# ADC_AD7761BSTZ.net
KiCad netlist of a schematic drawn in EAGLE
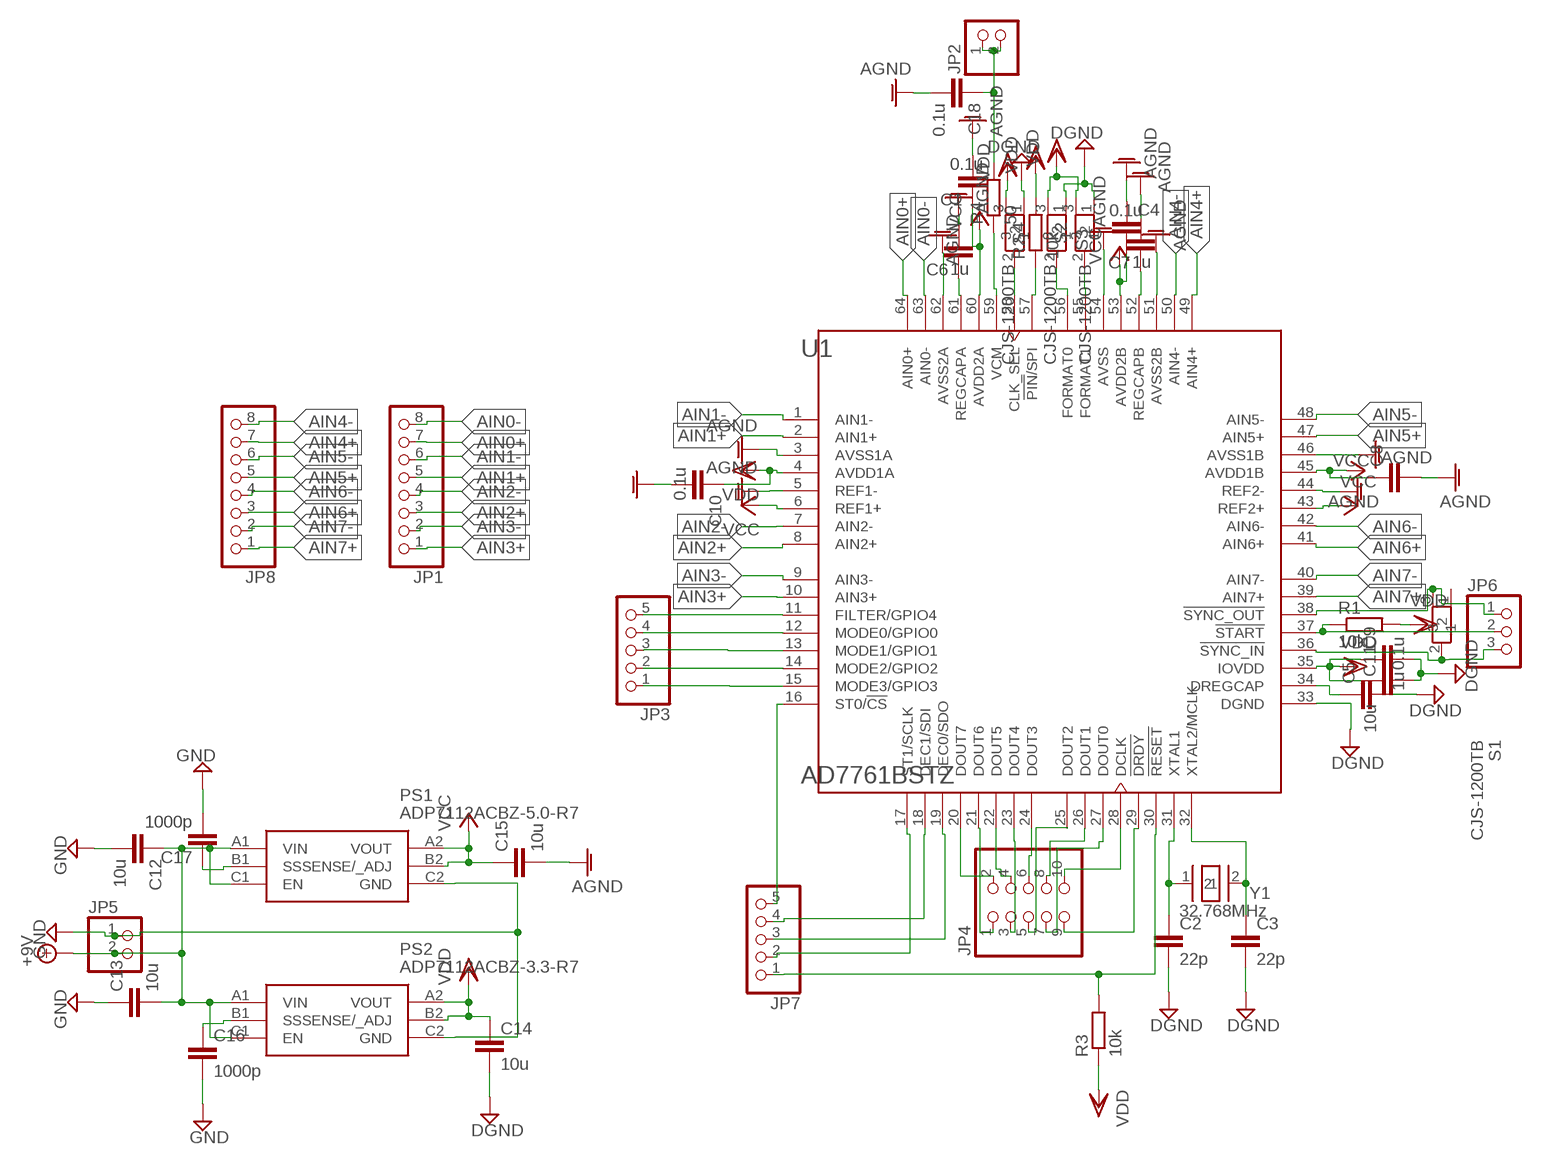
[diagram p0: schematic, sheet 1]

(export (version "E")
  (design (tool "Eeschema 10.0.6"))
  (components
    (comp (ref "C1")
      (value "0.1u")
      (footprint "eagle-import:C1608")
      (libsource (lib "eagle-import") (part "C-EUC1608"))
    )
    (comp (ref "C2")
      (value "22p")
      (footprint "eagle-import:C1608")
      (libsource (lib "eagle-import") (part "C-EUC1608"))
    )
    (comp (ref "C3")
      (value "22p")
      (footprint "eagle-import:C1608")
      (libsource (lib "eagle-import") (part "C-EUC1608"))
    )
    (comp (ref "C4")
      (value "0.1u")
      (footprint "eagle-import:C1608")
      (libsource (lib "eagle-import") (part "C-EUC1608"))
    )
    (comp (ref "C5")
      (value "10u")
      (footprint "eagle-import:C2012")
      (libsource (lib "eagle-import") (part "C-EUC2012"))
    )
    (comp (ref "C6")
      (value "1u")
      (footprint "eagle-import:C1608")
      (libsource (lib "eagle-import") (part "C-EUC1608"))
    )
    (comp (ref "C7")
      (value "1u")
      (footprint "eagle-import:C1608")
      (libsource (lib "eagle-import") (part "C-EUC1608"))
    )
    (comp (ref "C8")
      (value "0.1u")
      (footprint "eagle-import:C1608")
      (libsource (lib "eagle-import") (part "C-EUC1608"))
    )
    (comp (ref "C9")
      (value "0.1u")
      (footprint "eagle-import:C1608")
      (libsource (lib "eagle-import") (part "C-EUC1608"))
    )
    (comp (ref "C10")
      (value "0.1u")
      (footprint "eagle-import:C1608")
      (libsource (lib "eagle-import") (part "C-EUC1608"))
    )
    (comp (ref "C11")
      (value "1u")
      (footprint "eagle-import:C1608")
      (libsource (lib "eagle-import") (part "C-EUC1608"))
    )
    (comp (ref "C12")
      (value "10u")
      (footprint "eagle-import:C2012")
      (libsource (lib "eagle-import") (part "C-EUC2012"))
    )
    (comp (ref "C13")
      (value "10u")
      (footprint "eagle-import:C2012")
      (libsource (lib "eagle-import") (part "C-EUC2012"))
    )
    (comp (ref "C14")
      (value "10u")
      (footprint "eagle-import:C2012")
      (libsource (lib "eagle-import") (part "C-EUC2012"))
    )
    (comp (ref "C15")
      (value "10u")
      (footprint "eagle-import:C2012")
      (libsource (lib "eagle-import") (part "C-EUC2012"))
    )
    (comp (ref "C16")
      (value "1000p")
      (footprint "eagle-import:C1608")
      (libsource (lib "eagle-import") (part "C-EUC1608"))
    )
    (comp (ref "C17")
      (value "1000p")
      (footprint "eagle-import:C1608")
      (libsource (lib "eagle-import") (part "C-EUC1608"))
    )
    (comp (ref "C18")
      (value "0.1u")
      (footprint "eagle-import:C1608")
      (libsource (lib "eagle-import") (part "C-EUC1608"))
    )
    (comp (ref "JP1")
      (value "PINHD-1X8")
      (footprint "eagle-import:1X08")
      (libsource (lib "eagle-import") (part "PINHD-1X8"))
    )
    (comp (ref "JP2")
      (value "PINHD-1X2")
      (footprint "eagle-import:1X02")
      (libsource (lib "eagle-import") (part "PINHD-1X2"))
    )
    (comp (ref "JP3")
      (value "PINHD-1X5")
      (footprint "eagle-import:1X05")
      (libsource (lib "eagle-import") (part "PINHD-1X5"))
    )
    (comp (ref "JP4")
      (value "PINHD-2X5")
      (footprint "eagle-import:2X05")
      (libsource (lib "eagle-import") (part "PINHD-2X5"))
    )
    (comp (ref "JP5")
      (value "PINHD-1X2")
      (footprint "eagle-import:1X02")
      (libsource (lib "eagle-import") (part "PINHD-1X2"))
    )
    (comp (ref "JP6")
      (value "PINHD-1X3")
      (footprint "eagle-import:1X03")
      (libsource (lib "eagle-import") (part "PINHD-1X3"))
    )
    (comp (ref "JP7")
      (value "PINHD-1X5")
      (footprint "eagle-import:1X05")
      (libsource (lib "eagle-import") (part "PINHD-1X5"))
    )
    (comp (ref "JP8")
      (value "PINHD-1X8")
      (footprint "eagle-import:1X08")
      (libsource (lib "eagle-import") (part "PINHD-1X8"))
    )
    (comp (ref "PS1")
      (value "ADP7112ACBZ-5.0-R7")
      (footprint "eagle-import:BGA6C40P2X3_95X116X56")
      (fields
        (field (name "ARROW_PART_NUMBER") "ADP7112ACBZ-3.3-R7")
        (field (name "MOUSER_PART_NUMBER") "584-ADP7112ACBZ3.3R7")
      )
      (libsource (lib "eagle-import") (part "ADP7112ACBZ-3.3-R7"))
    )
    (comp (ref "PS2")
      (value "ADP7112ACBZ-3.3-R7")
      (footprint "eagle-import:BGA6C40P2X3_95X116X56")
      (fields (field (name "MOUSER_PART_NUMBER") "584-ADP7112ACBZ3.3R7"))
      (libsource (lib "eagle-import") (part "ADP7112ACBZ-3.3-R7"))
    )
    (comp (ref "R1")
      (value "10k")
      (footprint "eagle-import:R0603")
      (libsource (lib "eagle-import") (part "R-EU_R0603"))
    )
    (comp (ref "R2")
      (value "10k")
      (footprint "eagle-import:R0603")
      (libsource (lib "eagle-import") (part "R-EU_R0603"))
    )
    (comp (ref "R3")
      (value "10k")
      (footprint "eagle-import:R0603")
      (libsource (lib "eagle-import") (part "R-EU_R0603"))
    )
    (comp (ref "R4")
      (value "50")
      (footprint "eagle-import:R0603")
      (libsource (lib "eagle-import") (part "R-EU_R0603"))
    )
    (comp (ref "S1")
      (value "CJS-1200TB")
      (footprint "eagle-import:B-TYPE")
      (libsource (lib "eagle-import") (part "CJS-1200TB"))
    )
    (comp (ref "S2")
      (value "CJS-1200TB")
      (footprint "eagle-import:B-TYPE")
      (libsource (lib "eagle-import") (part "CJS-1200TB"))
    )
    (comp (ref "S3")
      (value "CJS-1200TB")
      (footprint "eagle-import:B-TYPE")
      (libsource (lib "eagle-import") (part "CJS-1200TB"))
    )
    (comp (ref "S4")
      (value "CJS-1200TB")
      (footprint "eagle-import:B-TYPE")
      (libsource (lib "eagle-import") (part "CJS-1200TB"))
    )
    (comp (ref "U1")
      (value "AD7761BSTZ")
      (footprint "eagle-import:QFP50P1200X1200X160-64N")
      (fields (field (name "MF") "Analog Devices"))
      (libsource (lib "eagle-import") (part "AD7761BSTZ"))
    )
    (comp (ref "Y1")
      (value "32.768MHz")
      (footprint "eagle-import:FC4SDCBMF24576T1")
      (fields
        (field (name "ARROW_PART_NUMBER") "FC4SDCBMF24.576-T1")
        (field (name "MOUSER_PART_NUMBER") "559-FC4SDCBMF24576T1")
      )
      (libsource (lib "eagle-import") (part "FC4SDCBMF24.576-T1"))
    )
  )
  (nets
    (net (code "1") (name "+9V") (class "Default")
      (node (ref "C12") (pin "1") (pinfunction "1_1") (pintype "passive"))
      (node (ref "C13") (pin "2") (pinfunction "2_2") (pintype "passive"))
      (node (ref "JP5") (pin "2") (pinfunction "2_2") (pintype "passive"))
      (node (ref "PS1") (pin "A1") (pinfunction "VIN_A1") (pintype "bidirectional"))
      (node (ref "PS1") (pin "C1") (pinfunction "EN_C1") (pintype "bidirectional"))
      (node (ref "PS2") (pin "A1") (pinfunction "VIN_A1") (pintype "bidirectional"))
      (node (ref "PS2") (pin "C1") (pinfunction "EN_C1") (pintype "bidirectional"))
    )
    (net (code "2") (name "AGND") (class "Default")
      (node (ref "C1") (pin "2") (pinfunction "2_2") (pintype "passive"))
      (node (ref "C10") (pin "2") (pinfunction "2_2") (pintype "passive"))
      (node (ref "C15") (pin "2") (pinfunction "2_2") (pintype "passive"))
      (node (ref "C18") (pin "2") (pinfunction "2_2") (pintype "passive"))
      (node (ref "C4") (pin "1") (pinfunction "1_1") (pintype "passive"))
      (node (ref "C6") (pin "2") (pinfunction "2_2") (pintype "passive"))
      (node (ref "C7") (pin "2") (pinfunction "2_2") (pintype "passive"))
      (node (ref "C8") (pin "2") (pinfunction "2_2") (pintype "passive"))
      (node (ref "U1") (pin "3") (pinfunction "AVSS1A_3") (pintype "power_in"))
      (node (ref "U1") (pin "44") (pinfunction "REF2-_44") (pintype "input"))
      (node (ref "U1") (pin "46") (pinfunction "AVSS1B_46") (pintype "power_in"))
      (node (ref "U1") (pin "5") (pinfunction "REF1-_5") (pintype "input"))
      (node (ref "U1") (pin "51") (pinfunction "AVSS2B_51") (pintype "power_in"))
      (node (ref "U1") (pin "54") (pinfunction "AVSS_54") (pintype "power_in"))
      (node (ref "U1") (pin "62") (pinfunction "AVSS2A_62") (pintype "power_in"))
    )
    (net (code "3") (name "AIN0+") (class "Default")
      (node (ref "JP1") (pin "7") (pinfunction "7_7") (pintype "passive"))
      (node (ref "U1") (pin "64") (pinfunction "AIN0+_64") (pintype "input"))
    )
    (net (code "4") (name "AIN0-") (class "Default")
      (node (ref "JP1") (pin "8") (pinfunction "8_8") (pintype "passive"))
      (node (ref "U1") (pin "63") (pinfunction "AIN0-_63") (pintype "input"))
    )
    (net (code "5") (name "AIN1+") (class "Default")
      (node (ref "JP1") (pin "5") (pinfunction "5_5") (pintype "passive"))
      (node (ref "U1") (pin "2") (pinfunction "AIN1+_2") (pintype "input"))
    )
    (net (code "6") (name "AIN1-") (class "Default")
      (node (ref "JP1") (pin "6") (pinfunction "6_6") (pintype "passive"))
      (node (ref "U1") (pin "1") (pinfunction "AIN1-_1") (pintype "input"))
    )
    (net (code "7") (name "AIN2+") (class "Default")
      (node (ref "JP1") (pin "3") (pinfunction "3_3") (pintype "passive"))
      (node (ref "U1") (pin "8") (pinfunction "AIN2+_8") (pintype "input"))
    )
    (net (code "8") (name "AIN2-") (class "Default")
      (node (ref "JP1") (pin "4") (pinfunction "4_4") (pintype "passive"))
      (node (ref "U1") (pin "7") (pinfunction "AIN2-_7") (pintype "input"))
    )
    (net (code "9") (name "AIN3+") (class "Default")
      (node (ref "JP1") (pin "1") (pinfunction "1_1") (pintype "passive"))
      (node (ref "U1") (pin "10") (pinfunction "AIN3+_10") (pintype "input"))
    )
    (net (code "10") (name "AIN3-") (class "Default")
      (node (ref "JP1") (pin "2") (pinfunction "2_2") (pintype "passive"))
      (node (ref "U1") (pin "9") (pinfunction "AIN3-_9") (pintype "input"))
    )
    (net (code "11") (name "AIN4+") (class "Default")
      (node (ref "JP8") (pin "7") (pinfunction "7_7") (pintype "passive"))
      (node (ref "U1") (pin "49") (pinfunction "AIN4+_49") (pintype "input"))
    )
    (net (code "12") (name "AIN4-") (class "Default")
      (node (ref "JP8") (pin "8") (pinfunction "8_8") (pintype "passive"))
      (node (ref "U1") (pin "50") (pinfunction "AIN4-_50") (pintype "input"))
    )
    (net (code "13") (name "AIN5+") (class "Default")
      (node (ref "JP8") (pin "5") (pinfunction "5_5") (pintype "passive"))
      (node (ref "U1") (pin "47") (pinfunction "AIN5+_47") (pintype "input"))
    )
    (net (code "14") (name "AIN5-") (class "Default")
      (node (ref "JP8") (pin "6") (pinfunction "6_6") (pintype "passive"))
      (node (ref "U1") (pin "48") (pinfunction "AIN5-_48") (pintype "input"))
    )
    (net (code "15") (name "AIN6+") (class "Default")
      (node (ref "JP8") (pin "3") (pinfunction "3_3") (pintype "passive"))
      (node (ref "U1") (pin "41") (pinfunction "AIN6+_41") (pintype "input"))
    )
    (net (code "16") (name "AIN6-") (class "Default")
      (node (ref "JP8") (pin "4") (pinfunction "4_4") (pintype "passive"))
      (node (ref "U1") (pin "42") (pinfunction "AIN6-_42") (pintype "input"))
    )
    (net (code "17") (name "AIN7+") (class "Default")
      (node (ref "JP8") (pin "1") (pinfunction "1_1") (pintype "passive"))
      (node (ref "U1") (pin "39") (pinfunction "AIN7+_39") (pintype "input"))
    )
    (net (code "18") (name "AIN7-") (class "Default")
      (node (ref "JP8") (pin "2") (pinfunction "2_2") (pintype "passive"))
      (node (ref "U1") (pin "40") (pinfunction "AIN7-_40") (pintype "input"))
    )
    (net (code "19") (name "DGND") (class "Default")
      (node (ref "C11") (pin "2") (pinfunction "2_2") (pintype "passive"))
      (node (ref "C14") (pin "2") (pinfunction "2_2") (pintype "passive"))
      (node (ref "C2") (pin "2") (pinfunction "2_2") (pintype "passive"))
      (node (ref "C3") (pin "2") (pinfunction "2_2") (pintype "passive"))
      (node (ref "C5") (pin "2") (pinfunction "2_2") (pintype "passive"))
      (node (ref "C9") (pin "2") (pinfunction "2_2") (pintype "passive"))
      (node (ref "S2") (pin "1") (pinfunction "1_1") (pintype "bidirectional"))
      (node (ref "S3") (pin "1") (pinfunction "1_1") (pintype "bidirectional"))
      (node (ref "S4") (pin "1") (pinfunction "1_1") (pintype "bidirectional"))
      (node (ref "U1") (pin "33") (pinfunction "DGND_33") (pintype "power_in"))
    )
    (net (code "20") (name "GND") (class "Default")
      (node (ref "C12") (pin "2") (pinfunction "2_2") (pintype "passive"))
      (node (ref "C13") (pin "1") (pinfunction "1_1") (pintype "passive"))
      (node (ref "C16") (pin "2") (pinfunction "2_2") (pintype "passive"))
      (node (ref "C17") (pin "2") (pinfunction "2_2") (pintype "passive"))
      (node (ref "JP5") (pin "1") (pinfunction "1_1") (pintype "passive"))
      (node (ref "PS1") (pin "C2") (pinfunction "GND_C2") (pintype "bidirectional"))
      (node (ref "PS2") (pin "C2") (pinfunction "GND_C2") (pintype "bidirectional"))
    )
    (net (code "21") (name "Net-(C18-Pad1)") (class "Default")
      (node (ref "C18") (pin "1") (pinfunction "1_1") (pintype "passive"))
      (node (ref "JP2") (pin "1") (pinfunction "1_1") (pintype "passive"))
      (node (ref "JP2") (pin "2") (pinfunction "2_2") (pintype "passive"))
      (node (ref "R4") (pin "2") (pinfunction "2_2") (pintype "passive"))
    )
    (net (code "22") (name "Net-(PS1-SS)") (class "Default")
      (node (ref "C17") (pin "1") (pinfunction "1_1") (pintype "passive"))
      (node (ref "PS1") (pin "B1") (pinfunction "SS_B1") (pintype "bidirectional"))
    )
    (net (code "23") (name "Net-(PS2-SS)") (class "Default")
      (node (ref "C16") (pin "1") (pinfunction "1_1") (pintype "passive"))
      (node (ref "PS2") (pin "B1") (pinfunction "SS_B1") (pintype "bidirectional"))
    )
    (net (code "24") (name "Net-(U1-CLK_SEL)") (class "Default")
      (node (ref "S4") (pin "2") (pinfunction "2_2") (pintype "bidirectional"))
      (node (ref "U1") (pin "58") (pinfunction "CLK_SEL_58") (pintype "input"))
    )
    (net (code "25") (name "Net-(U1-DCLK)") (class "Default")
      (node (ref "JP4") (pin "10") (pinfunction "10_10") (pintype "passive"))
      (node (ref "U1") (pin "28") (pinfunction "DCLK_28") (pintype "output"))
    )
    (net (code "26") (name "Net-(U1-DEC0{slash}SDO)") (class "Default")
      (node (ref "JP7") (pin "3") (pinfunction "3_3") (pintype "passive"))
      (node (ref "U1") (pin "19") (pinfunction "DEC0/SDO_19") (pintype "bidirectional"))
    )
    (net (code "27") (name "Net-(U1-DEC1{slash}SDI)") (class "Default")
      (node (ref "JP7") (pin "4") (pinfunction "4_4") (pintype "passive"))
      (node (ref "U1") (pin "18") (pinfunction "DEC1/SDI_18") (pintype "input"))
    )
    (net (code "28") (name "Net-(U1-DOUT0)") (class "Default")
      (node (ref "JP4") (pin "7") (pinfunction "7_7") (pintype "passive"))
      (node (ref "U1") (pin "27") (pinfunction "DOUT0_27") (pintype "output"))
    )
    (net (code "29") (name "Net-(U1-DOUT1)") (class "Default")
      (node (ref "JP4") (pin "8") (pinfunction "8_8") (pintype "passive"))
      (node (ref "U1") (pin "26") (pinfunction "DOUT1_26") (pintype "output"))
    )
    (net (code "30") (name "Net-(U1-DOUT2)") (class "Default")
      (node (ref "JP4") (pin "5") (pinfunction "5_5") (pintype "passive"))
      (node (ref "U1") (pin "25") (pinfunction "DOUT2_25") (pintype "output"))
    )
    (net (code "31") (name "Net-(U1-DOUT3)") (class "Default")
      (node (ref "JP4") (pin "6") (pinfunction "6_6") (pintype "passive"))
      (node (ref "U1") (pin "24") (pinfunction "DOUT3_24") (pintype "output"))
    )
    (net (code "32") (name "Net-(U1-DOUT4)") (class "Default")
      (node (ref "JP4") (pin "3") (pinfunction "3_3") (pintype "passive"))
      (node (ref "U1") (pin "23") (pinfunction "DOUT4_23") (pintype "output"))
    )
    (net (code "33") (name "Net-(U1-DOUT5)") (class "Default")
      (node (ref "JP4") (pin "4") (pinfunction "4_4") (pintype "passive"))
      (node (ref "U1") (pin "22") (pinfunction "DOUT5_22") (pintype "output"))
    )
    (net (code "34") (name "Net-(U1-DOUT6)") (class "Default")
      (node (ref "JP4") (pin "1") (pinfunction "1_1") (pintype "passive"))
      (node (ref "U1") (pin "21") (pinfunction "DOUT6_21") (pintype "output"))
    )
    (net (code "35") (name "Net-(U1-DOUT7)") (class "Default")
      (node (ref "JP4") (pin "2") (pinfunction "2_2") (pintype "passive"))
      (node (ref "U1") (pin "20") (pinfunction "DOUT7_20") (pintype "output"))
    )
    (net (code "36") (name "Net-(U1-DREGCAP)") (class "Default")
      (node (ref "C5") (pin "1") (pinfunction "1_1") (pintype "passive"))
      (node (ref "U1") (pin "34") (pinfunction "DREGCAP_34") (pintype "output"))
    )
    (net (code "37") (name "Net-(U1-FILTER{slash}GPIO4)") (class "Default")
      (node (ref "JP3") (pin "5") (pinfunction "5_5") (pintype "passive"))
      (node (ref "U1") (pin "11") (pinfunction "FILTER/GPIO4_11") (pintype "bidirectional"))
    )
    (net (code "38") (name "Net-(U1-FORMAT0)") (class "Default")
      (node (ref "S2") (pin "2") (pinfunction "2_2") (pintype "bidirectional"))
      (node (ref "U1") (pin "56") (pinfunction "FORMAT0_56") (pintype "input"))
    )
    (net (code "39") (name "Net-(U1-FORMAT1)") (class "Default")
      (node (ref "S3") (pin "2") (pinfunction "2_2") (pintype "bidirectional"))
      (node (ref "U1") (pin "55") (pinfunction "FORMAT1_55") (pintype "input"))
    )
    (net (code "40") (name "Net-(U1-MODE0{slash}GPIO0)") (class "Default")
      (node (ref "JP3") (pin "4") (pinfunction "4_4") (pintype "passive"))
      (node (ref "U1") (pin "12") (pinfunction "MODE0/GPIO0_12") (pintype "bidirectional"))
    )
    (net (code "41") (name "Net-(U1-MODE1{slash}GPIO1)") (class "Default")
      (node (ref "JP3") (pin "3") (pinfunction "3_3") (pintype "passive"))
      (node (ref "U1") (pin "13") (pinfunction "MODE1/GPIO1_13") (pintype "bidirectional"))
    )
    (net (code "42") (name "Net-(U1-MODE2{slash}GPIO2)") (class "Default")
      (node (ref "JP3") (pin "2") (pinfunction "2_2") (pintype "passive"))
      (node (ref "U1") (pin "14") (pinfunction "MODE2/GPIO2_14") (pintype "bidirectional"))
    )
    (net (code "43") (name "Net-(U1-MODE3{slash}GPIO3)") (class "Default")
      (node (ref "JP3") (pin "1") (pinfunction "1_1") (pintype "passive"))
      (node (ref "U1") (pin "15") (pinfunction "MODE3/GPIO3_15") (pintype "bidirectional"))
    )
    (net (code "44") (name "Net-(U1-REGCAPA)") (class "Default")
      (node (ref "C6") (pin "1") (pinfunction "1_1") (pintype "passive"))
      (node (ref "U1") (pin "61") (pinfunction "REGCAPA_61") (pintype "output"))
    )
    (net (code "45") (name "Net-(U1-REGCAPB)") (class "Default")
      (node (ref "C7") (pin "1") (pinfunction "1_1") (pintype "passive"))
      (node (ref "U1") (pin "52") (pinfunction "REGCAPB_52") (pintype "output"))
    )
    (net (code "46") (name "Net-(U1-ST0{slash}~{CS})") (class "Default")
      (node (ref "JP7") (pin "5") (pinfunction "5_5") (pintype "passive"))
      (node (ref "U1") (pin "16") (pinfunction "ST0/~{CS}_16") (pintype "input"))
    )
    (net (code "47") (name "Net-(U1-ST1{slash}SCLK)") (class "Default")
      (node (ref "JP7") (pin "2") (pinfunction "2_2") (pintype "passive"))
      (node (ref "U1") (pin "17") (pinfunction "ST1/SCLK_17") (pintype "input"))
    )
    (net (code "48") (name "Net-(U1-VCM)") (class "Default")
      (node (ref "R4") (pin "1") (pinfunction "1_1") (pintype "passive"))
      (node (ref "U1") (pin "59") (pinfunction "VCM_59") (pintype "output"))
    )
    (net (code "49") (name "Net-(U1-XTAL1)") (class "Default")
      (node (ref "C2") (pin "1") (pinfunction "1_1") (pintype "passive"))
      (node (ref "U1") (pin "31") (pinfunction "XTAL1_31") (pintype "input"))
      (node (ref "Y1") (pin "1") (pinfunction "1_1") (pintype "bidirectional"))
    )
    (net (code "50") (name "Net-(U1-XTAL2{slash}MCLK)") (class "Default")
      (node (ref "C3") (pin "1") (pinfunction "1_1") (pintype "passive"))
      (node (ref "U1") (pin "32") (pinfunction "XTAL2/MCLK_32") (pintype "input"))
      (node (ref "Y1") (pin "2") (pinfunction "2_2") (pintype "bidirectional"))
    )
    (net (code "51") (name "Net-(U1-~{DRDY})") (class "Default")
      (node (ref "JP4") (pin "9") (pinfunction "9_9") (pintype "passive"))
      (node (ref "U1") (pin "29") (pinfunction "~{DRDY}_29") (pintype "output"))
    )
    (net (code "52") (name "Net-(U1-~{PIN}{slash}SPI)") (class "Default")
      (node (ref "R2") (pin "1") (pinfunction "1_1") (pintype "passive"))
      (node (ref "U1") (pin "57") (pinfunction "~{PIN}/SPI_57") (pintype "input"))
    )
    (net (code "53") (name "Net-(U1-~{RESET})") (class "Default")
      (node (ref "JP7") (pin "1") (pinfunction "1_1") (pintype "passive"))
      (node (ref "R3") (pin "2") (pinfunction "2_2") (pintype "passive"))
      (node (ref "U1") (pin "30") (pinfunction "~{RESET}_30") (pintype "input"))
    )
    (net (code "54") (name "Net-(U1-~{START})") (class "Default")
      (node (ref "JP6") (pin "2") (pinfunction "2_2") (pintype "passive"))
      (node (ref "R1") (pin "1") (pinfunction "1_1") (pintype "passive"))
      (node (ref "U1") (pin "37") (pinfunction "~{START}_37") (pintype "input"))
    )
    (net (code "55") (name "Net-(U1-~{SYNC_IN})") (class "Default")
      (node (ref "JP6") (pin "3") (pinfunction "3_3") (pintype "passive"))
      (node (ref "S1") (pin "2") (pinfunction "2_2") (pintype "bidirectional"))
      (node (ref "U1") (pin "36") (pinfunction "~{SYNC_IN}_36") (pintype "input"))
    )
    (net (code "56") (name "Net-(U1-~{SYNC_OUT})") (class "Default")
      (node (ref "JP6") (pin "1") (pinfunction "1_1") (pintype "passive"))
      (node (ref "S1") (pin "3") (pinfunction "3_3") (pintype "bidirectional"))
      (node (ref "U1") (pin "38") (pinfunction "~{SYNC_OUT}_38") (pintype "output"))
    )
    (net (code "57") (name "VCC") (class "Default")
      (node (ref "C1") (pin "1") (pinfunction "1_1") (pintype "passive"))
      (node (ref "C15") (pin "1") (pinfunction "1_1") (pintype "passive"))
      (node (ref "C4") (pin "2") (pinfunction "2_2") (pintype "passive"))
      (node (ref "C8") (pin "1") (pinfunction "1_1") (pintype "passive"))
      (node (ref "PS1") (pin "A2") (pinfunction "VOUT_A2") (pintype "bidirectional"))
      (node (ref "PS1") (pin "B2") (pinfunction "SENSE/_ADJ_B2") (pintype "bidirectional"))
      (node (ref "U1") (pin "43") (pinfunction "REF2+_43") (pintype "input"))
      (node (ref "U1") (pin "45") (pinfunction "AVDD1B_45") (pintype "power_in"))
      (node (ref "U1") (pin "53") (pinfunction "AVDD2B_53") (pintype "power_in"))
      (node (ref "U1") (pin "6") (pinfunction "REF1+_6") (pintype "input"))
      (node (ref "U1") (pin "60") (pinfunction "AVDD2A_60") (pintype "power_in"))
    )
    (net (code "58") (name "VDD") (class "Default")
      (node (ref "C10") (pin "1") (pinfunction "1_1") (pintype "passive"))
      (node (ref "C11") (pin "1") (pinfunction "1_1") (pintype "passive"))
      (node (ref "C14") (pin "1") (pinfunction "1_1") (pintype "passive"))
      (node (ref "C9") (pin "1") (pinfunction "1_1") (pintype "passive"))
      (node (ref "PS2") (pin "A2") (pinfunction "VOUT_A2") (pintype "bidirectional"))
      (node (ref "PS2") (pin "B2") (pinfunction "SENSE/_ADJ_B2") (pintype "bidirectional"))
      (node (ref "R1") (pin "2") (pinfunction "2_2") (pintype "passive"))
      (node (ref "R2") (pin "2") (pinfunction "2_2") (pintype "passive"))
      (node (ref "R3") (pin "1") (pinfunction "1_1") (pintype "passive"))
      (node (ref "S2") (pin "3") (pinfunction "3_3") (pintype "bidirectional"))
      (node (ref "S3") (pin "3") (pinfunction "3_3") (pintype "bidirectional"))
      (node (ref "S4") (pin "3") (pinfunction "3_3") (pintype "bidirectional"))
      (node (ref "U1") (pin "35") (pinfunction "IOVDD_35") (pintype "power_in"))
      (node (ref "U1") (pin "4") (pinfunction "AVDD1A_4") (pintype "power_in"))
    )
    (net (code "59") (name "unconnected-(S1-Pad1)") (class "Default")
      (node (ref "S1") (pin "1") (pinfunction "1_1") (pintype "bidirectional"))
    )
  )
)
